# Power_Regulation.net
KiCad netlist of a schematic drawn in Altium Designer
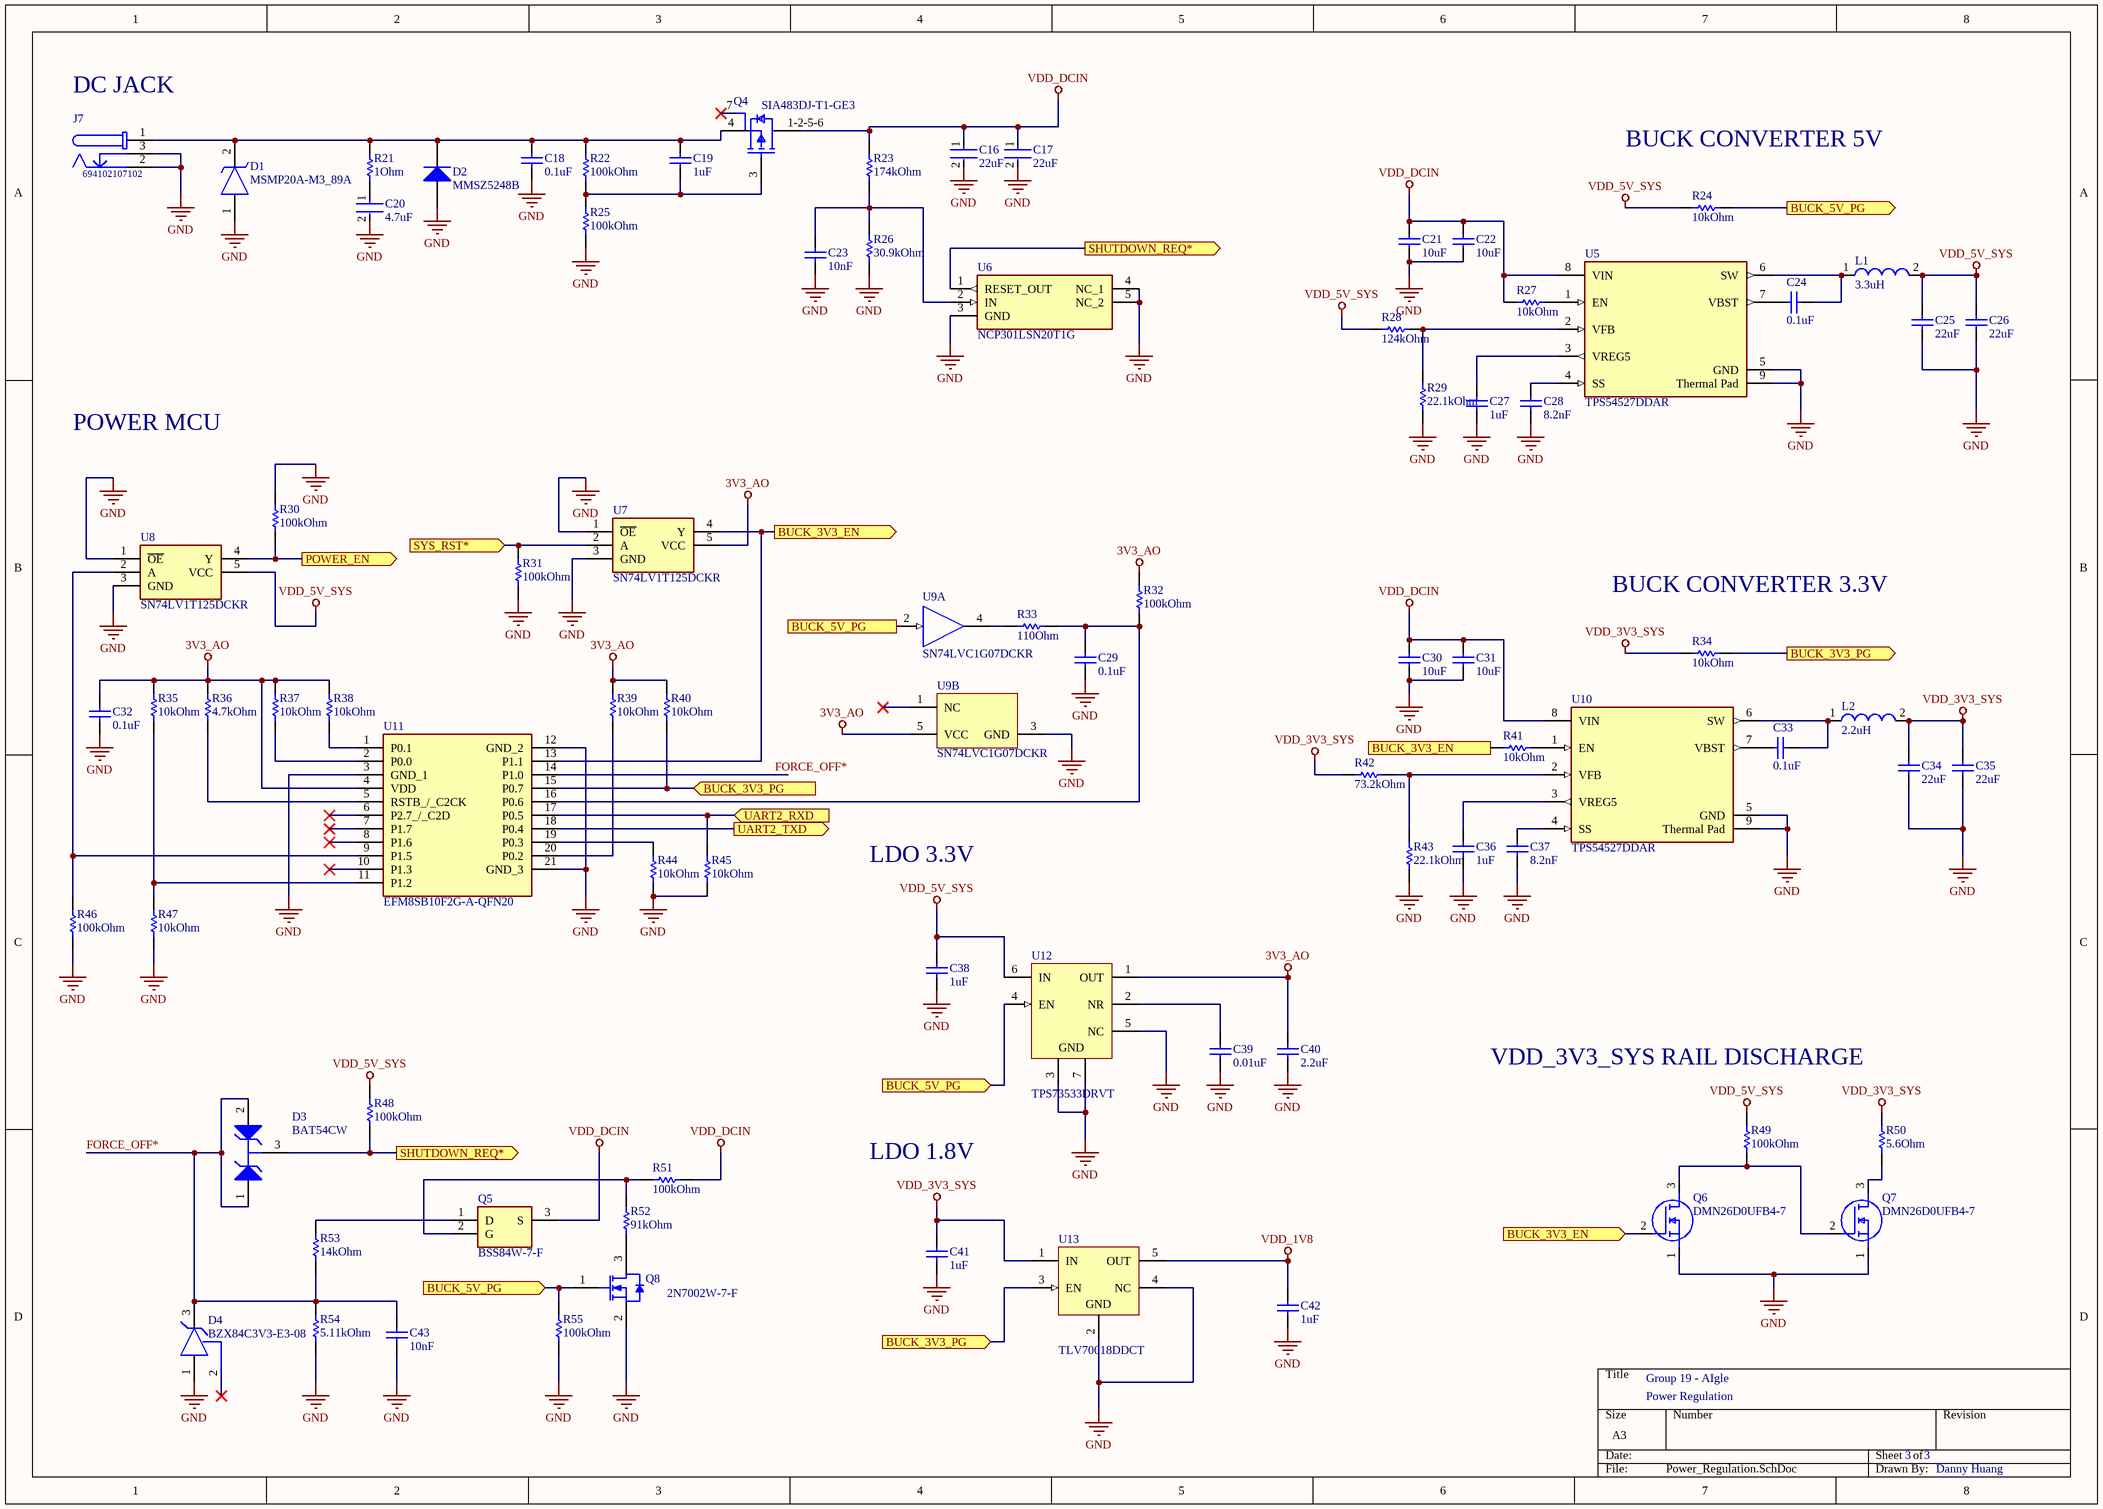
[diagram p0: Power_Regulation.SchDoc]

(export (version "E")
  (design (tool "Eeschema 10.0.6"))
  (components
    (comp (ref "C16")
      (value "22uF")
      (footprint "FP-GRM21-0_2-MFG")
      (description "CAP CER 22UF 25V X5R 0805")
      (fields (field (name "TOLERANCE") "20%") (field (name "MANUFACTURER PART NUMBER") "GRM21BR61E226ME44L"))
      (libsource (lib "Altium Content Vault") (part "b4654b650e69147ec39a6b967a45e02"))
    )
    (comp (ref "C17")
      (value "22uF")
      (footprint "FP-GRM21-0_2-MFG")
      (description "CAP CER 22UF 25V X5R 0805")
      (fields (field (name "TOLERANCE") "20%") (field (name "MANUFACTURER PART NUMBER") "GRM21BR61E226ME44L"))
      (libsource (lib "Altium Content Vault") (part "b4654b650e69147ec39a6b967a45e02"))
    )
    (comp (ref "C18")
      (value "0.1uF")
      (footprint "CAPC1005X55X30NL05T10")
      (fields (field (name "MANUFACTURER") "Kemet") (field (name "PART NUMBER") "C0402C104K9RACTU"))
      (libsource (lib "Altium Content Vault") (part "CAP"))
    )
    (comp (ref "C19")
      (value "1uF")
      (footprint "CAPC1608X90X35LL10T15")
      (fields (field (name "MANUFACTURER") "Murata") (field (name "PART NUMBER") "GRM188R61E105KA12D"))
      (libsource (lib "Altium Content Vault") (part "CAP"))
    )
    (comp (ref "C20")
      (value "4.7uF")
      (footprint "FP-C0603-CG-MFG")
      (description "CAP CER 4.7UF 6.3V X5R 0603")
      (fields (field (name "TOLERANCE") "10%") (field (name "MANUFACTURER") "Kemet"))
      (libsource (lib "Altium Content Vault") (part "11868f565c42a9108669ba33697ecf6"))
    )
    (comp (ref "C21")
      (value "10uF")
      (footprint "CAPC1608X90X35NL10T15")
      (fields (field (name "PART NUMBER") "GRM188R60J106ME47D") (field (name "MANUFACTURER") "Murata"))
      (libsource (lib "Altium Content Vault") (part "CAP"))
    )
    (comp (ref "C22")
      (value "10uF")
      (footprint "CAPC1608X90X35NL10T15")
      (fields (field (name "PART NUMBER") "GRM188R60J106ME47D") (field (name "MANUFACTURER") "Murata"))
      (libsource (lib "Altium Content Vault") (part "CAP"))
    )
    (comp (ref "C23")
      (value "10nF")
      (footprint "CAPC1005X55X30NL05T10")
      (fields (field (name "MANUFACTURER") "Kemet") (field (name "PART NUMBER") "C0402C103K4RACTU"))
      (libsource (lib "Altium Content Vault") (part "CAP"))
    )
    (comp (ref "C24")
      (value "0.1uF")
      (footprint "CAPC1005X55X30NL05T10")
      (fields (field (name "MANUFACTURER") "Kemet") (field (name "PART NUMBER") "C0402C104K9RACTU"))
      (libsource (lib "Altium Content Vault") (part "CAP"))
    )
    (comp (ref "C25")
      (value "22uF")
      (footprint "CAPC1608X100X20ML10")
      (description "Chip Capacitor, 22 uF, +/- 20%, 6.3 V, -55 to 85 degC, 1608 (0603 Metric), RoHS, Tape and Reel")
      (fields
        (field (name "TOLERANCE") "±20%")
        (field (name "PCN PART NUMBER") "MLCCPartNumberChange30/Nov/2012")
      )
      (libsource (lib "Altium Content Vault") (part "CAP-NP-2"))
    )
    (comp (ref "C26")
      (value "22uF")
      (footprint "CAPC1608X100X20ML10")
      (description "Chip Capacitor, 22 uF, +/- 20%, 6.3 V, -55 to 85 degC, 1608 (0603 Metric), RoHS, Tape and Reel")
      (fields
        (field (name "TOLERANCE") "±20%")
        (field (name "PCN PART NUMBER") "MLCCPartNumberChange30/Nov/2012")
      )
      (libsource (lib "Altium Content Vault") (part "CAP-NP-2"))
    )
    (comp (ref "C27")
      (value "1uF")
      (footprint "CAPC1005X60X30ML05T10")
      (fields (field (name "PART NUMBER") "C0402C105K9PAC7867") (field (name "MANUFACTURER") "Kemet"))
      (libsource (lib "Altium Content Vault") (part "CAP"))
    )
    (comp (ref "C28")
      (value "8.2nF")
      (footprint "CAPC1005X55X30ML05T10")
      (fields (field (name "PART NUMBER") "C0402C822K5RACTU") (field (name "MANUFACTURER") "Kemet"))
      (libsource (lib "Altium Content Vault") (part "CAP"))
    )
    (comp (ref "C29")
      (value "0.1uF")
      (footprint "CAPC1005X55X30NL05T10")
      (fields (field (name "MANUFACTURER") "Kemet") (field (name "PART NUMBER") "C0402C104K9RACTU"))
      (libsource (lib "Altium Content Vault") (part "CAP"))
    )
    (comp (ref "C30")
      (value "10uF")
      (footprint "CAPC1608X90X35NL10T15")
      (fields (field (name "PART NUMBER") "GRM188R60J106ME47D") (field (name "MANUFACTURER") "Murata"))
      (libsource (lib "Altium Content Vault") (part "CAP"))
    )
    (comp (ref "C31")
      (value "10uF")
      (footprint "CAPC1608X90X35NL10T15")
      (fields (field (name "PART NUMBER") "GRM188R60J106ME47D") (field (name "MANUFACTURER") "Murata"))
      (libsource (lib "Altium Content Vault") (part "CAP"))
    )
    (comp (ref "C32")
      (value "0.1uF")
      (footprint "CAPC1005X55X30NL05T10")
      (fields (field (name "MANUFACTURER") "Kemet") (field (name "PART NUMBER") "C0402C104K9RACTU"))
      (libsource (lib "Altium Content Vault") (part "CAP"))
    )
    (comp (ref "C33")
      (value "0.1uF")
      (footprint "CAPC1005X55X30NL05T10")
      (fields (field (name "MANUFACTURER") "Kemet") (field (name "PART NUMBER") "C0402C104K9RACTU"))
      (libsource (lib "Altium Content Vault") (part "CAP"))
    )
    (comp (ref "C34")
      (value "22uF")
      (footprint "CAPC1608X100X20ML10")
      (description "Chip Capacitor, 22 uF, +/- 20%, 6.3 V, -55 to 85 degC, 1608 (0603 Metric), RoHS, Tape and Reel")
      (fields
        (field (name "TOLERANCE") "±20%")
        (field (name "PCN PART NUMBER") "MLCCPartNumberChange30/Nov/2012")
      )
      (libsource (lib "Altium Content Vault") (part "CAP-NP-2"))
    )
    (comp (ref "C35")
      (value "22uF")
      (footprint "CAPC1608X100X20ML10")
      (description "Chip Capacitor, 22 uF, +/- 20%, 6.3 V, -55 to 85 degC, 1608 (0603 Metric), RoHS, Tape and Reel")
      (fields
        (field (name "TOLERANCE") "±20%")
        (field (name "PCN PART NUMBER") "MLCCPartNumberChange30/Nov/2012")
      )
      (libsource (lib "Altium Content Vault") (part "CAP-NP-2"))
    )
    (comp (ref "C36")
      (value "1uF")
      (footprint "CAPC1005X60X30ML05T10")
      (fields (field (name "PART NUMBER") "C0402C105K9PAC7867") (field (name "MANUFACTURER") "Kemet"))
      (libsource (lib "Altium Content Vault") (part "CAP"))
    )
    (comp (ref "C37")
      (value "8.2nF")
      (footprint "CAPC1005X55X30ML05T10")
      (fields (field (name "PART NUMBER") "C0402C822K5RACTU") (field (name "MANUFACTURER") "Kemet"))
      (libsource (lib "Altium Content Vault") (part "CAP"))
    )
    (comp (ref "C38")
      (value "1uF")
      (footprint "CAPC1005X60X30ML05T10")
      (fields (field (name "PART NUMBER") "C0402C105K9PAC7867") (field (name "MANUFACTURER") "Kemet"))
      (libsource (lib "Altium Content Vault") (part "CAP"))
    )
    (comp (ref "C39")
      (value "0.01uF")
      (footprint "CAPC1005X55X30LL05T10")
      (fields (field (name "MANUFACTURER") "Kemet") (field (name "PART NUMBER") "C0402C103K9RACTU"))
      (libsource (lib "Altium Content Vault") (part "CAP"))
    )
    (comp (ref "C40")
      (value "2.2uF")
      (footprint "CAPC1005X60X30NL05T10")
      (fields (field (name "PART NUMBER") "C0402C225K9PACTU") (field (name "MANUFACTURER") "Kemet"))
      (libsource (lib "Altium Content Vault") (part "CAP"))
    )
    (comp (ref "C41")
      (value "1uF")
      (footprint "CAPC1005X60X30ML05T10")
      (fields (field (name "PART NUMBER") "C0402C105K9PAC7867") (field (name "MANUFACTURER") "Kemet"))
      (libsource (lib "Altium Content Vault") (part "CAP"))
    )
    (comp (ref "C42")
      (value "1uF")
      (footprint "CAPC1005X60X30ML05T10")
      (fields (field (name "PART NUMBER") "C0402C105K9PAC7867") (field (name "MANUFACTURER") "Kemet"))
      (libsource (lib "Altium Content Vault") (part "CAP"))
    )
    (comp (ref "C43")
      (value "10nF")
      (footprint "CAPC1005X55X30NL05T10")
      (fields (field (name "MANUFACTURER") "Kemet") (field (name "PART NUMBER") "C0402C103K4RACTU"))
      (libsource (lib "Altium Content Vault") (part "CAP"))
    )
    (comp (ref "D1")
      (value "MSMP20A-M3_89A")
      (footprint "SamacSys:MICROSMP(ESMP)")
      (description "TVS Diode (Uni-directional)")
      (fields
        (field (name "MANUFACTURER_PART_NUMBER") "MSMP20A-M3/89A")
        (field (name "MOUSER PART NUMBER") "78-MSMP20A-M389A")
      )
      (libsource (lib "*") (part "MSMP20A-M3_89A"))
    )
    (comp (ref "D2")
      (value "MMSZ5248B")
      (footprint "FAIR-SOD-123-2_V")
      (description "Zener Diode, 18 V, -55 to 150 degC, 2-Pin SOD-123, RoHS, Tape and Reel")
      (fields (field (name "MANUFACTURER") "FairchildSemiconductor"))
      (libsource (lib "Altium Content Vault") (part "D-AK-2"))
    )
    (comp (ref "D3")
      (value "BAT54CW")
      (footprint "NXP-SOT323-3_L")
      (description "SOT-323 Plastic-Encapsulated Diode")
      (fields (field (name "MANUFACTURER") "NXP Semiconductors"))
      (libsource (lib "Altium Content Vault") (part "NXP-DSKY-A1K3-3"))
    )
    (comp (ref "D4")
      (value "BZX84C3V3-E3-08")
      (footprint "FP-6_541-5014_01-4-MFG")
      (description "DIODE ZENER 3.3V 300MW SOT23")
      (fields
        (field (name "MANUFACTURER") "Vishay")
        (field (name "OCTOPART") "https://octopart.com/bzx84c3v3-e3-08-vishay-30324846")
      )
      (libsource (lib "Altium Content Vault") (part "926c53f45a061d244664d41e4b83f83"))
    )
    (comp (ref "J7")
      (value "694102107102")
      (footprint "694102107102")
      (fields (field (name "MANUFACTURER") "Wurth Elektronik") (field (name "PUBLISHER") "WurthElektronik"))
      (libsource (lib "Altium Content Vault") (part "WE-JACK-2CD3-RN"))
    )
    (comp (ref "L1")
      (value "3.3uH")
      (footprint "SMD 0806")
      (description "Power Multilayer Inductor WE-PMI, L=3.30 µH")
      (fields (field (name "PARTNUMBER") "74479776233") (field (name "MANUFACTURER") "Wuerth Elektronik"))
      (libsource (lib "Altium Content Vault") (part "PAS-IND-INDUCTOR-2"))
    )
    (comp (ref "L2")
      (value "2.2uH")
      (footprint "SMD 0805-Low profile")
      (description "Power Multilayer Inductor WE-PMI, L=2.20 µH")
      (fields (field (name "MANUFACTURER") "Wuerth Elektronik") (field (name "PARTNUMBER") "74479774222"))
      (libsource (lib "Altium Content Vault") (part "PAS-IND-INDUCTOR-2"))
    )
    (comp (ref "Q4")
      (value "SIA483DJ-T1-GE3")
      (footprint "FP-C-07431-MFG")
      (description "MOSFET P-CH 30V 12A SC70-6")
      (fields
        (field (name "OCTOPART") "https://octopart.com/sia483dj-t1-ge3-vishay-45727624")
        (field (name "MANUFACTURER") "Vishay")
      )
      (libsource (lib "Altium Content Vault") (part "150fc967241ccd8041086e7d050c159"))
    )
    (comp (ref "Q5")
      (value "BSS84W-7-F")
      (footprint "SamacSys:SOT65P210X110-3N")
      (description "Undefined or Miscellaneous")
      (fields (field (name "MOUSER PART NUMBER") "621-BSS84W-F"))
      (libsource (lib "*") (part "BSS84W-7-F"))
    )
    (comp (ref "Q6")
      (value "DMN26D0UFB4-7")
      (footprint "SamacSys:DMN26D0UFB47")
      (description "MOSFET (N-Channel)")
      (fields (field (name "MOUSER PART NUMBER") "621-DMN26D0UFB4-7"))
      (libsource (lib "*") (part "DMN26D0UFB4-7"))
    )
    (comp (ref "Q7")
      (value "DMN26D0UFB4-7")
      (footprint "SamacSys:DMN26D0UFB47")
      (description "MOSFET (N-Channel)")
      (fields (field (name "MOUSER PART NUMBER") "621-DMN26D0UFB4-7"))
      (libsource (lib "*") (part "DMN26D0UFB4-7"))
    )
    (comp (ref "Q8")
      (value "2N7002W-7-F")
      (footprint "DIOD-SOT323-3_V")
      (fields (field (name "MANUFACTURER") "DiodesIncorporated"))
      (libsource (lib "Altium Content Vault") (part "NEMOS-GSD-3"))
    )
    (comp (ref "R21")
      (value "1Ohm")
      (footprint "RESC1005X40X25ML05T05")
      (fields (field (name "PART NUMBER") "CRCW04021R00FKED") (field (name "MANUFACTURER") "Vishay Dale"))
      (libsource (lib "Altium Content Vault") (part "RES"))
    )
    (comp (ref "R22")
      (value "100kOhm")
      (footprint "RESC1005X40X25ML05T05")
      (description "Chip Resistor, 100 KOhm, +/- 1%, 0.63 W, -55 to 155 degC, 0402 (1005 Metric), RoHS, Tape and Reel")
      (fields (field (name "TOLERANCE") "1%"))
      (libsource (lib "Altium Content Vault") (part "RES-2"))
    )
    (comp (ref "R23")
      (value "174kOhm")
      (footprint "RESC1005X40X25LL05T05")
      (fields (field (name "MANUFACTURER") "Vishay Dale") (field (name "PART NUMBER") "CRCW0402174KFKED"))
      (libsource (lib "Altium Content Vault") (part "RES"))
    )
    (comp (ref "R24")
      (value "10kOhm")
      (footprint "RESC1005X40X25NL05T05")
      (fields (field (name "MANUFACTURER") "Vishay Dale") (field (name "PART NUMBER") "CRCW040210K0JNED"))
      (libsource (lib "Altium Content Vault") (part "RES"))
    )
    (comp (ref "R25")
      (value "100kOhm")
      (footprint "RESC1005X40X25ML05T05")
      (description "Chip Resistor, 100 KOhm, +/- 1%, 0.63 W, -55 to 155 degC, 0402 (1005 Metric), RoHS, Tape and Reel")
      (fields (field (name "TOLERANCE") "1%"))
      (libsource (lib "Altium Content Vault") (part "RES-2"))
    )
    (comp (ref "R26")
      (value "30.9kOhm")
      (footprint "RESC1005X40X25LL05T05")
      (fields (field (name "PART NUMBER") "CRCW040230K9FKED") (field (name "MANUFACTURER") "Vishay Dale"))
      (libsource (lib "Altium Content Vault") (part "RES"))
    )
    (comp (ref "R27")
      (value "10kOhm")
      (footprint "RESC1005X40X25NL05T05")
      (fields (field (name "MANUFACTURER") "Vishay Dale") (field (name "PART NUMBER") "CRCW040210K0JNED"))
      (libsource (lib "Altium Content Vault") (part "RES"))
    )
    (comp (ref "R28")
      (value "124kOhm")
      (footprint "RESC1005X40X25ML05T05")
      (fields (field (name "MANUFACTURER") "Vishay Dale") (field (name "PART NUMBER") "CRCW0402124KFKED"))
      (libsource (lib "Altium Content Vault") (part "RES"))
    )
    (comp (ref "R29")
      (value "22.1kOhm")
      (footprint "RESC1005X40X25ML05T05")
      (fields (field (name "MANUFACTURER") "Vishay Dale") (field (name "PART NUMBER") "CRCW040222K1FKED"))
      (libsource (lib "Altium Content Vault") (part "RES"))
    )
    (comp (ref "R30")
      (value "100kOhm")
      (footprint "RESC1005X40X25ML05T05")
      (description "Chip Resistor, 100 KOhm, +/- 1%, 0.63 W, -55 to 155 degC, 0402 (1005 Metric), RoHS, Tape and Reel")
      (fields (field (name "TOLERANCE") "1%"))
      (libsource (lib "Altium Content Vault") (part "RES-2"))
    )
    (comp (ref "R31")
      (value "100kOhm")
      (footprint "RESC1005X40X25ML05T05")
      (description "Chip Resistor, 100 KOhm, +/- 1%, 0.63 W, -55 to 155 degC, 0402 (1005 Metric), RoHS, Tape and Reel")
      (fields (field (name "TOLERANCE") "1%"))
      (libsource (lib "Altium Content Vault") (part "RES-2"))
    )
    (comp (ref "R32")
      (value "100kOhm")
      (footprint "RESC1005X40X25ML05T05")
      (description "Chip Resistor, 100 KOhm, +/- 1%, 0.63 W, -55 to 155 degC, 0402 (1005 Metric), RoHS, Tape and Reel")
      (fields (field (name "TOLERANCE") "1%"))
      (libsource (lib "Altium Content Vault") (part "RES-2"))
    )
    (comp (ref "R33")
      (value "110Ohm")
      (footprint "RESC1005X40X25LL05T05")
      (fields (field (name "PART NUMBER") "CRCW0402110RJNED") (field (name "MANUFACTURER") "Vishay Dale"))
      (libsource (lib "Altium Content Vault") (part "RES"))
    )
    (comp (ref "R34")
      (value "10kOhm")
      (footprint "RESC1005X40X25NL05T05")
      (fields (field (name "MANUFACTURER") "Vishay Dale") (field (name "PART NUMBER") "CRCW040210K0JNED"))
      (libsource (lib "Altium Content Vault") (part "RES"))
    )
    (comp (ref "R35")
      (value "10kOhm")
      (footprint "RESC1005X40X25NL05T05")
      (fields (field (name "MANUFACTURER") "Vishay Dale") (field (name "PART NUMBER") "CRCW040210K0FKED"))
      (libsource (lib "Altium Content Vault") (part "RES"))
    )
    (comp (ref "R36")
      (value "4.7kOhm")
      (footprint "RESC1005X40X25ML05T05")
      (fields
        (field (name "PART NUMBER") "CRCW04024K70JNED")
        (field (name "MANUFACTURER") "Vishay BCcomponents")
      )
      (libsource (lib "Altium Content Vault") (part "RES"))
    )
    (comp (ref "R37")
      (value "10kOhm")
      (footprint "RESC1005X40X25NL05T05")
      (fields (field (name "MANUFACTURER") "Vishay Dale") (field (name "PART NUMBER") "CRCW040210K0FKED"))
      (libsource (lib "Altium Content Vault") (part "RES"))
    )
    (comp (ref "R38")
      (value "10kOhm")
      (footprint "RESC1005X40X25NL05T05")
      (fields (field (name "MANUFACTURER") "Vishay Dale") (field (name "PART NUMBER") "CRCW040210K0FKED"))
      (libsource (lib "Altium Content Vault") (part "RES"))
    )
    (comp (ref "R39")
      (value "10kOhm")
      (footprint "RESC1005X40X25NL05T05")
      (fields (field (name "MANUFACTURER") "Vishay Dale") (field (name "PART NUMBER") "CRCW040210K0FKED"))
      (libsource (lib "Altium Content Vault") (part "RES"))
    )
    (comp (ref "R40")
      (value "10kOhm")
      (footprint "RESC1005X40X25NL05T05")
      (fields (field (name "MANUFACTURER") "Vishay Dale") (field (name "PART NUMBER") "CRCW040210K0FKED"))
      (libsource (lib "Altium Content Vault") (part "RES"))
    )
    (comp (ref "R41")
      (value "10kOhm")
      (footprint "RESC1005X40X25NL05T05")
      (fields (field (name "MANUFACTURER") "Vishay Dale") (field (name "PART NUMBER") "CRCW040210K0JNED"))
      (libsource (lib "Altium Content Vault") (part "RES"))
    )
    (comp (ref "R42")
      (value "73.2kOhm")
      (footprint "RESC1005X40X25ML05T05")
      (fields (field (name "PART NUMBER") "CRCW040273K2FKED") (field (name "MANUFACTURER") "Vishay Dale"))
      (libsource (lib "Altium Content Vault") (part "RES"))
    )
    (comp (ref "R43")
      (value "22.1kOhm")
      (footprint "RESC1005X40X25ML05T05")
      (fields (field (name "MANUFACTURER") "Vishay Dale") (field (name "PART NUMBER") "CRCW040222K1FKED"))
      (libsource (lib "Altium Content Vault") (part "RES"))
    )
    (comp (ref "R44")
      (value "10kOhm")
      (footprint "RESC1005X40X25NL05T05")
      (fields (field (name "MANUFACTURER") "Vishay Dale") (field (name "PART NUMBER") "CRCW040210K0FKED"))
      (libsource (lib "Altium Content Vault") (part "RES"))
    )
    (comp (ref "R45")
      (value "10kOhm")
      (footprint "RESC1005X40X25NL05T05")
      (fields (field (name "MANUFACTURER") "Vishay Dale") (field (name "PART NUMBER") "CRCW040210K0FKED"))
      (libsource (lib "Altium Content Vault") (part "RES"))
    )
    (comp (ref "R46")
      (value "100kOhm")
      (footprint "RESC1005X40X25ML05T05")
      (description "Chip Resistor, 100 KOhm, +/- 1%, 0.63 W, -55 to 155 degC, 0402 (1005 Metric), RoHS, Tape and Reel")
      (fields (field (name "TOLERANCE") "1%"))
      (libsource (lib "Altium Content Vault") (part "RES-2"))
    )
    (comp (ref "R47")
      (value "10kOhm")
      (footprint "RESC1005X40X25NL05T05")
      (fields (field (name "MANUFACTURER") "Vishay Dale") (field (name "PART NUMBER") "CRCW040210K0FKED"))
      (libsource (lib "Altium Content Vault") (part "RES"))
    )
    (comp (ref "R48")
      (value "100kOhm")
      (footprint "RESC1005X40X25ML05T05")
      (description "Chip Resistor, 100 KOhm, +/- 1%, 0.63 W, -55 to 155 degC, 0402 (1005 Metric), RoHS, Tape and Reel")
      (fields (field (name "TOLERANCE") "1%"))
      (libsource (lib "Altium Content Vault") (part "RES-2"))
    )
    (comp (ref "R49")
      (value "100kOhm")
      (footprint "RESC1005X40X25ML05T05")
      (description "Chip Resistor, 100 KOhm, +/- 1%, 0.63 W, -55 to 155 degC, 0402 (1005 Metric), RoHS, Tape and Reel")
      (fields (field (name "TOLERANCE") "1%"))
      (libsource (lib "Altium Content Vault") (part "RES-2"))
    )
    (comp (ref "R50")
      (value "5.6Ohm")
      (footprint "RESC1005X40X25ML05T05")
      (fields (field (name "PART NUMBER") "ERJ-2GEJ5R6X") (field (name "MANUFACTURER") "Panasonic"))
      (libsource (lib "Altium Content Vault") (part "RES"))
    )
    (comp (ref "R51")
      (value "100kOhm")
      (footprint "RESC1005X40X25ML05T05")
      (description "Chip Resistor, 100 KOhm, +/- 1%, 0.63 W, -55 to 155 degC, 0402 (1005 Metric), RoHS, Tape and Reel")
      (fields (field (name "TOLERANCE") "1%"))
      (libsource (lib "Altium Content Vault") (part "RES-2"))
    )
    (comp (ref "R52")
      (value "91kOhm")
      (footprint "RESC1005X40X25ML05T05")
      (fields (field (name "MANUFACTURER") "Vishay Dale") (field (name "PART NUMBER") "CRCW040291K0JNED"))
      (libsource (lib "Altium Content Vault") (part "RES"))
    )
    (comp (ref "R53")
      (value "14kOhm")
      (footprint "RESC1005X40X25LL05T05")
      (fields (field (name "MANUFACTURER") "Vishay Dale") (field (name "PART NUMBER") "CRCW040214K0FKED"))
      (libsource (lib "Altium Content Vault") (part "RES"))
    )
    (comp (ref "R54")
      (value "5.11kOhm")
      (footprint "RESC1005X40X25LL05T05")
      (fields (field (name "MANUFACTURER") "Vishay Dale") (field (name "PART NUMBER") "CRCW04025K11FKED"))
      (libsource (lib "Altium Content Vault") (part "RES"))
    )
    (comp (ref "R55")
      (value "100kOhm")
      (footprint "RESC1005X40X25ML05T05")
      (description "Chip Resistor, 100 KOhm, +/- 1%, 0.63 W, -55 to 155 degC, 0402 (1005 Metric), RoHS, Tape and Reel")
      (fields (field (name "TOLERANCE") "1%"))
      (libsource (lib "Altium Content Vault") (part "RES-2"))
    )
    (comp (ref "U5")
      (value "TPS54527DDAR")
      (footprint "FP-DDA0008E-MFG")
      (description "IC REG BUCK ADJUSTABLE 5A 8SOPWR")
      (fields
        (field (name "OCTOPART") "https://octopart.com/tps54527ddar-texas+instruments-20362751")
        (field (name "MANUFACTURER") "Texas Instruments")
      )
      (libsource (lib "Altium Content Vault") (part "5ee31ad572399e68e8e3131d2eca248"))
    )
    (comp (ref "U6")
      (value "NCP301LSN20T1G")
      (footprint "SamacSys:SOT95P275X110-5N")
      (description "Integrated Circuit")
      (fields (field (name "MOUSER PART NUMBER") "863-NCP301LSN20T1G"))
      (libsource (lib "*") (part "NCP301LSN20T1G"))
    )
    (comp (ref "U7")
      (value "SN74LV1T125DCKR")
      (footprint "SamacSys:SOT65P210X110-5N")
      (description "Integrated Circuit")
      (fields (field (name "MOUSER PART NUMBER") "595-SN74LV1T125DCKR"))
      (libsource (lib "*") (part "SN74LV1T125DCKR"))
    )
    (comp (ref "U8")
      (value "SN74LV1T125DCKR")
      (footprint "SamacSys:SOT65P210X110-5N")
      (description "Integrated Circuit")
      (fields (field (name "MOUSER PART NUMBER") "595-SN74LV1T125DCKR"))
      (libsource (lib "*") (part "SN74LV1T125DCKR"))
    )
    (comp (ref "U9")
      (value "SN74LVC1G07DCKR")
      (footprint "DCK0005A_M")
      (description "Single Buffer/Driver With Open-Drain Output, DCK0005A, LARGE T&R")
      (fields
        (field (name "GENERIC PART NUMBER") "SN74LVC1G07")
        (field (name "MANUFACTURER") "Texas Instruments")
      )
      (libsource (lib "Altium Content Vault") (part "TI-SN74XXX1G07-5"))
    )
    (comp (ref "U10")
      (value "TPS54527DDAR")
      (footprint "FP-DDA0008E-MFG")
      (description "IC REG BUCK ADJUSTABLE 5A 8SOPWR")
      (fields
        (field (name "OCTOPART") "https://octopart.com/tps54527ddar-texas+instruments-20362751")
        (field (name "MANUFACTURER") "Texas Instruments")
      )
      (libsource (lib "Altium Content Vault") (part "5ee31ad572399e68e8e3131d2eca248"))
    )
    (comp (ref "U11")
      (value "EFM8SB10F2G-A-QFN20")
      (footprint "SamacSys:EFM8SB10F8GAQFN20R")
      (description "Integrated Circuit")
      (fields (field (name "MOUSER PART NUMBER") "634-8SB10F2GAQF20"))
      (libsource (lib "*") (part "EFM8SB10F2G-A-QFN20"))
    )
    (comp (ref "U12")
      (value "TPS73533DRVT")
      (footprint "DRV0006A_V")
      (fields (field (name "MANUFACTURER") "Texas Instruments"))
      (libsource (lib "Altium Content Vault") (part "TI-TPS7XXXXX-DRV6-1600X1000TP"))
    )
    (comp (ref "U13")
      (value "TLV70018DDCT")
      (footprint "DDC0005A_L")
      (fields (field (name "MANUFACTURER") "Texas Instruments"))
      (libsource (lib "Altium Content Vault") (part "TI-TXX7XXXX-5"))
    )
  )
  (nets
    (net (code "1") (name "/BUCK_3V3_EN") (class "Default")
      (node (ref "Q6") (pin "2") (pinfunction "G_2") (pintype "passive"))
      (node (ref "R41") (pin "2") (pinfunction "2_2") (pintype "passive"))
      (node (ref "U11") (pin "13") (pinfunction "P1.1_13") (pintype "passive"))
      (node (ref "U7") (pin "4") (pinfunction "Y_4") (pintype "passive"))
    )
    (net (code "2") (name "/BUCK_3V3_PG") (class "Default")
      (node (ref "R34") (pin "1") (pinfunction "1_1") (pintype "passive"))
      (node (ref "R40") (pin "1") (pinfunction "1_1") (pintype "passive"))
      (node (ref "U11") (pin "15") (pinfunction "P0.7_15") (pintype "passive"))
      (node (ref "U13") (pin "3") (pinfunction "EN_3") (pintype "input"))
    )
    (net (code "3") (name "/BUCK_5V_PG") (class "Default")
      (node (ref "Q8") (pin "1") (pinfunction "G_1") (pintype "passive"))
      (node (ref "R24") (pin "1") (pinfunction "1_1") (pintype "passive"))
      (node (ref "R55") (pin "2") (pinfunction "2_2") (pintype "passive"))
      (node (ref "U12") (pin "4") (pinfunction "EN_4") (pintype "input"))
      (node (ref "U9") (pin "2") (pinfunction "A_2") (pintype "input"))
    )
    (net (code "4") (name "/FORCE_OFF*") (class "Default")
      (node (ref "C43") (pin "2") (pinfunction "2_2") (pintype "passive"))
      (node (ref "D3") (pin "1") (pinfunction "A1_1") (pintype "passive"))
      (node (ref "D3") (pin "2") (pinfunction "A2_2") (pintype "passive"))
      (node (ref "D4") (pin "3") (pinfunction "C_3") (pintype "passive"))
      (node (ref "R53") (pin "1") (pinfunction "1_1") (pintype "passive"))
      (node (ref "R54") (pin "2") (pinfunction "2_2") (pintype "passive"))
      (node (ref "U11") (pin "14") (pinfunction "P1.0_14") (pintype "passive"))
    )
    (net (code "5") (name "/POWER_EN") (class "Default")
      (node (ref "R30") (pin "1") (pinfunction "1_1") (pintype "passive"))
      (node (ref "U8") (pin "4") (pinfunction "Y_4") (pintype "passive"))
    )
    (net (code "6") (name "/SHUTDOWN_REQ*") (class "Default")
      (node (ref "D3") (pin "3") (pinfunction "K_3") (pintype "passive"))
      (node (ref "R48") (pin "1") (pinfunction "1_1") (pintype "passive"))
      (node (ref "U6") (pin "1") (pinfunction "RESET_OUT_1") (pintype "output"))
    )
    (net (code "7") (name "/SYS_RST*") (class "Default")
      (node (ref "R31") (pin "2") (pinfunction "2_2") (pintype "passive"))
      (node (ref "U7") (pin "2") (pinfunction "A_2") (pintype "passive"))
    )
    (net (code "8") (name "/UART2_RXD") (class "Default")
      (node (ref "R45") (pin "2") (pinfunction "2_2") (pintype "passive"))
      (node (ref "U11") (pin "17") (pinfunction "P0.5_17") (pintype "passive"))
    )
    (net (code "9") (name "/UART2_TXD") (class "Default")
      (node (ref "U11") (pin "18") (pinfunction "P0.4_18") (pintype "passive"))
    )
    (net (code "10") (name "3V3_AO") (class "Default")
      (node (ref "C32") (pin "1") (pinfunction "1_1") (pintype "passive"))
      (node (ref "C40") (pin "2") (pinfunction "2_2") (pintype "passive"))
      (node (ref "R32") (pin "2") (pinfunction "2_2") (pintype "passive"))
      (node (ref "R35") (pin "2") (pinfunction "2_2") (pintype "passive"))
      (node (ref "R36") (pin "2") (pinfunction "2_2") (pintype "passive"))
      (node (ref "R37") (pin "2") (pinfunction "2_2") (pintype "passive"))
      (node (ref "R38") (pin "2") (pinfunction "2_2") (pintype "passive"))
      (node (ref "R39") (pin "2") (pinfunction "2_2") (pintype "passive"))
      (node (ref "R40") (pin "2") (pinfunction "2_2") (pintype "passive"))
      (node (ref "U11") (pin "4") (pinfunction "VDD_4") (pintype "passive"))
      (node (ref "U12") (pin "1") (pinfunction "OUT_1") (pintype "power_in"))
      (node (ref "U7") (pin "5") (pinfunction "VCC_5") (pintype "passive"))
      (node (ref "U9") (pin "5") (pinfunction "VCC_5") (pintype "power_in"))
    )
    (net (code "11") (name "GND") (class "Default")
      (node (ref "C16") (pin "2") (pinfunction "2_2") (pintype "passive"))
      (node (ref "C17") (pin "2") (pinfunction "2_2") (pintype "passive"))
      (node (ref "C18") (pin "2") (pinfunction "2_2") (pintype "passive"))
      (node (ref "C20") (pin "2") (pinfunction "2_2") (pintype "passive"))
      (node (ref "C21") (pin "1") (pinfunction "1_1") (pintype "passive"))
      (node (ref "C22") (pin "1") (pinfunction "1_1") (pintype "passive"))
      (node (ref "C23") (pin "1") (pinfunction "1_1") (pintype "passive"))
      (node (ref "C25") (pin "1") (pinfunction "1_1") (pintype "passive"))
      (node (ref "C26") (pin "1") (pinfunction "1_1") (pintype "passive"))
      (node (ref "C27") (pin "1") (pinfunction "1_1") (pintype "passive"))
      (node (ref "C28") (pin "1") (pinfunction "1_1") (pintype "passive"))
      (node (ref "C29") (pin "2") (pinfunction "2_2") (pintype "passive"))
      (node (ref "C30") (pin "1") (pinfunction "1_1") (pintype "passive"))
      (node (ref "C31") (pin "1") (pinfunction "1_1") (pintype "passive"))
      (node (ref "C32") (pin "2") (pinfunction "2_2") (pintype "passive"))
      (node (ref "C34") (pin "1") (pinfunction "1_1") (pintype "passive"))
      (node (ref "C35") (pin "1") (pinfunction "1_1") (pintype "passive"))
      (node (ref "C36") (pin "1") (pinfunction "1_1") (pintype "passive"))
      (node (ref "C37") (pin "1") (pinfunction "1_1") (pintype "passive"))
      (node (ref "C38") (pin "1") (pinfunction "1_1") (pintype "passive"))
      (node (ref "C39") (pin "1") (pinfunction "1_1") (pintype "passive"))
      (node (ref "C40") (pin "1") (pinfunction "1_1") (pintype "passive"))
      (node (ref "C41") (pin "1") (pinfunction "1_1") (pintype "passive"))
      (node (ref "C42") (pin "1") (pinfunction "1_1") (pintype "passive"))
      (node (ref "C43") (pin "1") (pinfunction "1_1") (pintype "passive"))
      (node (ref "D1") (pin "1") (pinfunction "A_1") (pintype "passive"))
      (node (ref "D2") (pin "1") (pinfunction "A_1") (pintype "passive"))
      (node (ref "D4") (pin "1") (pinfunction "A_1") (pintype "passive"))
      (node (ref "J7") (pin "2") (pinfunction "2_2") (pintype "passive"))
      (node (ref "J7") (pin "3") (pinfunction "3_3") (pintype "passive"))
      (node (ref "Q6") (pin "1") (pinfunction "S_1") (pintype "passive"))
      (node (ref "Q7") (pin "1") (pinfunction "S_1") (pintype "passive"))
      (node (ref "Q8") (pin "2") (pinfunction "S_2") (pintype "passive"))
      (node (ref "R25") (pin "2") (pinfunction "2_2") (pintype "passive"))
      (node (ref "R26") (pin "1") (pinfunction "1_1") (pintype "passive"))
      (node (ref "R29") (pin "1") (pinfunction "1_1") (pintype "passive"))
      (node (ref "R30") (pin "2") (pinfunction "2_2") (pintype "passive"))
      (node (ref "R31") (pin "1") (pinfunction "1_1") (pintype "passive"))
      (node (ref "R43") (pin "1") (pinfunction "1_1") (pintype "passive"))
      (node (ref "R44") (pin "1") (pinfunction "1_1") (pintype "passive"))
      (node (ref "R45") (pin "1") (pinfunction "1_1") (pintype "passive"))
      (node (ref "R46") (pin "1") (pinfunction "1_1") (pintype "passive"))
      (node (ref "R47") (pin "1") (pinfunction "1_1") (pintype "passive"))
      (node (ref "R54") (pin "1") (pinfunction "1_1") (pintype "passive"))
      (node (ref "R55") (pin "1") (pinfunction "1_1") (pintype "passive"))
      (node (ref "U10") (pin "5") (pinfunction "GND_5") (pintype "power_in"))
      (node (ref "U10") (pin "9") (pinfunction "Thermal_Pad_9") (pintype "power_in"))
      (node (ref "U11") (pin "12") (pinfunction "GND_2_12") (pintype "passive"))
      (node (ref "U11") (pin "21") (pinfunction "GND_3_21") (pintype "passive"))
      (node (ref "U11") (pin "3") (pinfunction "GND_1_3") (pintype "passive"))
      (node (ref "U12") (pin "3") (pinfunction "GND_3") (pintype "power_in"))
      (node (ref "U12") (pin "5") (pinfunction "NC_5") (pintype "passive"))
      (node (ref "U12") (pin "7") (pinfunction "GND_7") (pintype "power_in"))
      (node (ref "U13") (pin "2") (pinfunction "GND_2") (pintype "power_in"))
      (node (ref "U13") (pin "4") (pinfunction "NC_4") (pintype "passive"))
      (node (ref "U5") (pin "5") (pinfunction "GND_5") (pintype "power_in"))
      (node (ref "U5") (pin "9") (pinfunction "Thermal_Pad_9") (pintype "power_in"))
      (node (ref "U6") (pin "3") (pinfunction "GND_3") (pintype "power_in"))
      (node (ref "U6") (pin "4") (pinfunction "NC_1_4") (pintype "passive"))
      (node (ref "U6") (pin "5") (pinfunction "NC_2_5") (pintype "passive"))
      (node (ref "U7") (pin "1") (pinfunction "~{OE}_1") (pintype "passive"))
      (node (ref "U7") (pin "3") (pinfunction "GND_3") (pintype "passive"))
      (node (ref "U8") (pin "1") (pinfunction "~{OE}_1") (pintype "passive"))
      (node (ref "U8") (pin "3") (pinfunction "GND_3") (pintype "passive"))
      (node (ref "U9") (pin "3") (pinfunction "GND_3") (pintype "power_in"))
    )
    (net (code "12") (name "Net-(C20-Pad1)") (class "Default")
      (node (ref "C20") (pin "1") (pinfunction "1_1") (pintype "passive"))
      (node (ref "R21") (pin "1") (pinfunction "1_1") (pintype "passive"))
    )
    (net (code "13") (name "Net-(D1-K)") (class "Default")
      (node (ref "C18") (pin "1") (pinfunction "1_1") (pintype "passive"))
      (node (ref "C19") (pin "2") (pinfunction "2_2") (pintype "passive"))
      (node (ref "D1") (pin "2") (pinfunction "K_2") (pintype "passive"))
      (node (ref "D2") (pin "2") (pinfunction "K_2") (pintype "passive"))
      (node (ref "J7") (pin "1") (pinfunction "1_1") (pintype "passive"))
      (node (ref "Q4") (pin "4") (pinfunction "S_4") (pintype "passive"))
      (node (ref "R21") (pin "2") (pinfunction "2_2") (pintype "passive"))
      (node (ref "R22") (pin "1") (pinfunction "1_1") (pintype "passive"))
    )
    (net (code "14") (name "Net-(Q4-G)") (class "Default")
      (node (ref "C19") (pin "1") (pinfunction "1_1") (pintype "passive"))
      (node (ref "Q4") (pin "3") (pinfunction "G_3") (pintype "passive"))
      (node (ref "R22") (pin "2") (pinfunction "2_2") (pintype "passive"))
      (node (ref "R25") (pin "1") (pinfunction "1_1") (pintype "passive"))
    )
    (net (code "15") (name "Net-(Q5-D)") (class "Default")
      (node (ref "Q5") (pin "1") (pinfunction "D_1") (pintype "passive"))
      (node (ref "R53") (pin "2") (pinfunction "2_2") (pintype "passive"))
    )
    (net (code "16") (name "Net-(Q5-G)") (class "Default")
      (node (ref "Q5") (pin "2") (pinfunction "G_2") (pintype "passive"))
      (node (ref "R51") (pin "2") (pinfunction "2_2") (pintype "passive"))
      (node (ref "R52") (pin "2") (pinfunction "2_2") (pintype "passive"))
    )
    (net (code "17") (name "Net-(Q6-D)") (class "Default")
      (node (ref "Q6") (pin "3") (pinfunction "D_3") (pintype "passive"))
      (node (ref "Q7") (pin "2") (pinfunction "G_2") (pintype "passive"))
      (node (ref "R49") (pin "1") (pinfunction "1_1") (pintype "passive"))
    )
    (net (code "18") (name "Net-(Q7-D)") (class "Default")
      (node (ref "Q7") (pin "3") (pinfunction "D_3") (pintype "passive"))
      (node (ref "R50") (pin "1") (pinfunction "1_1") (pintype "passive"))
    )
    (net (code "19") (name "Net-(Q8-D)") (class "Default")
      (node (ref "Q8") (pin "3") (pinfunction "D_3") (pintype "passive"))
      (node (ref "R52") (pin "1") (pinfunction "1_1") (pintype "passive"))
    )
    (net (code "20") (name "Net-(U5-EN)") (class "Default")
      (node (ref "R27") (pin "1") (pinfunction "1_1") (pintype "passive"))
      (node (ref "U5") (pin "1") (pinfunction "EN_1") (pintype "input"))
    )
    (net (code "21") (name "Net-(U5-SS)") (class "Default")
      (node (ref "C28") (pin "2") (pinfunction "2_2") (pintype "passive"))
      (node (ref "U5") (pin "4") (pinfunction "SS_4") (pintype "input"))
    )
    (net (code "22") (name "Net-(U5-SW)") (class "Default")
      (node (ref "C24") (pin "1") (pinfunction "1_1") (pintype "passive"))
      (node (ref "L1") (pin "1") (pinfunction "1_1") (pintype "passive"))
      (node (ref "U5") (pin "6") (pinfunction "SW_6") (pintype "output"))
    )
    (net (code "23") (name "Net-(U5-VBST)") (class "Default")
      (node (ref "C24") (pin "2") (pinfunction "2_2") (pintype "passive"))
      (node (ref "U5") (pin "7") (pinfunction "VBST_7") (pintype "output"))
    )
    (net (code "24") (name "Net-(U5-VFB)") (class "Default")
      (node (ref "R28") (pin "2") (pinfunction "2_2") (pintype "passive"))
      (node (ref "R29") (pin "2") (pinfunction "2_2") (pintype "passive"))
      (node (ref "U5") (pin "2") (pinfunction "VFB_2") (pintype "input"))
    )
    (net (code "25") (name "Net-(U5-VREG5)") (class "Default")
      (node (ref "C27") (pin "2") (pinfunction "2_2") (pintype "passive"))
      (node (ref "U5") (pin "3") (pinfunction "VREG5_3") (pintype "output"))
    )
    (net (code "26") (name "Net-(U6-IN)") (class "Default")
      (node (ref "C23") (pin "2") (pinfunction "2_2") (pintype "passive"))
      (node (ref "R23") (pin "1") (pinfunction "1_1") (pintype "passive"))
      (node (ref "R26") (pin "2") (pinfunction "2_2") (pintype "passive"))
      (node (ref "U6") (pin "2") (pinfunction "IN_2") (pintype "input"))
    )
    (net (code "27") (name "Net-(U9A-Y)") (class "Default")
      (node (ref "R33") (pin "1") (pinfunction "1_1") (pintype "passive"))
      (node (ref "U9") (pin "4") (pinfunction "Y_4") (pintype "open_collector"))
    )
    (net (code "28") (name "Net-(U10-EN)") (class "Default")
      (node (ref "R41") (pin "1") (pinfunction "1_1") (pintype "passive"))
      (node (ref "U10") (pin "1") (pinfunction "EN_1") (pintype "input"))
    )
    (net (code "29") (name "Net-(U10-SS)") (class "Default")
      (node (ref "C37") (pin "2") (pinfunction "2_2") (pintype "passive"))
      (node (ref "U10") (pin "4") (pinfunction "SS_4") (pintype "input"))
    )
    (net (code "30") (name "Net-(U10-SW)") (class "Default")
      (node (ref "C33") (pin "1") (pinfunction "1_1") (pintype "passive"))
      (node (ref "L2") (pin "1") (pinfunction "1_1") (pintype "passive"))
      (node (ref "U10") (pin "6") (pinfunction "SW_6") (pintype "output"))
    )
    (net (code "31") (name "Net-(U10-VBST)") (class "Default")
      (node (ref "C33") (pin "2") (pinfunction "2_2") (pintype "passive"))
      (node (ref "U10") (pin "7") (pinfunction "VBST_7") (pintype "output"))
    )
    (net (code "32") (name "Net-(U10-VFB)") (class "Default")
      (node (ref "R42") (pin "2") (pinfunction "2_2") (pintype "passive"))
      (node (ref "R43") (pin "2") (pinfunction "2_2") (pintype "passive"))
      (node (ref "U10") (pin "2") (pinfunction "VFB_2") (pintype "input"))
    )
    (net (code "33") (name "Net-(U10-VREG5)") (class "Default")
      (node (ref "C36") (pin "2") (pinfunction "2_2") (pintype "passive"))
      (node (ref "U10") (pin "3") (pinfunction "VREG5_3") (pintype "output"))
    )
    (net (code "34") (name "Net-(U11-P0.0)") (class "Default")
      (node (ref "R37") (pin "1") (pinfunction "1_1") (pintype "passive"))
      (node (ref "U11") (pin "2") (pinfunction "P0.0_2") (pintype "passive"))
    )
    (net (code "35") (name "Net-(U11-P0.1)") (class "Default")
      (node (ref "R38") (pin "1") (pinfunction "1_1") (pintype "passive"))
      (node (ref "U11") (pin "1") (pinfunction "P0.1_1") (pintype "passive"))
    )
    (net (code "36") (name "Net-(U11-P0.2)") (class "Default")
      (node (ref "R39") (pin "1") (pinfunction "1_1") (pintype "passive"))
      (node (ref "U11") (pin "20") (pinfunction "P0.2_20") (pintype "passive"))
    )
    (net (code "37") (name "Net-(U11-P0.3)") (class "Default")
      (node (ref "R44") (pin "2") (pinfunction "2_2") (pintype "passive"))
      (node (ref "U11") (pin "19") (pinfunction "P0.3_19") (pintype "passive"))
    )
    (net (code "38") (name "Net-(U11-P0.6)") (class "Default")
      (node (ref "C29") (pin "1") (pinfunction "1_1") (pintype "passive"))
      (node (ref "R32") (pin "1") (pinfunction "1_1") (pintype "passive"))
      (node (ref "R33") (pin "2") (pinfunction "2_2") (pintype "passive"))
      (node (ref "U11") (pin "16") (pinfunction "P0.6_16") (pintype "passive"))
    )
    (net (code "39") (name "Net-(U11-P1.2)") (class "Default")
      (node (ref "R35") (pin "1") (pinfunction "1_1") (pintype "passive"))
      (node (ref "R47") (pin "2") (pinfunction "2_2") (pintype "passive"))
      (node (ref "U11") (pin "11") (pinfunction "P1.2_11") (pintype "passive"))
    )
    (net (code "40") (name "Net-(U11-P1.5)") (class "Default")
      (node (ref "R46") (pin "2") (pinfunction "2_2") (pintype "passive"))
      (node (ref "U11") (pin "9") (pinfunction "P1.5_9") (pintype "passive"))
      (node (ref "U8") (pin "2") (pinfunction "A_2") (pintype "passive"))
    )
    (net (code "41") (name "Net-(U11-RSTB_{slash}_C2CK)") (class "Default")
      (node (ref "R36") (pin "1") (pinfunction "1_1") (pintype "passive"))
      (node (ref "U11") (pin "5") (pinfunction "RSTB_/_C2CK_5") (pintype "passive"))
    )
    (net (code "42") (name "Net-(U12-NR)") (class "Default")
      (node (ref "C39") (pin "2") (pinfunction "2_2") (pintype "passive"))
      (node (ref "U12") (pin "2") (pinfunction "NR_2") (pintype "passive"))
    )
    (net (code "43") (name "VDD_1V8") (class "Default")
      (node (ref "C42") (pin "2") (pinfunction "2_2") (pintype "passive"))
      (node (ref "U13") (pin "5") (pinfunction "OUT_5") (pintype "power_in"))
    )
    (net (code "44") (name "VDD_3V3_SYS") (class "Default")
      (node (ref "C34") (pin "2") (pinfunction "2_2") (pintype "passive"))
      (node (ref "C35") (pin "2") (pinfunction "2_2") (pintype "passive"))
      (node (ref "C41") (pin "2") (pinfunction "2_2") (pintype "passive"))
      (node (ref "L2") (pin "2") (pinfunction "2_2") (pintype "passive"))
      (node (ref "R34") (pin "2") (pinfunction "2_2") (pintype "passive"))
      (node (ref "R42") (pin "1") (pinfunction "1_1") (pintype "passive"))
      (node (ref "R50") (pin "2") (pinfunction "2_2") (pintype "passive"))
      (node (ref "U13") (pin "1") (pinfunction "IN_1") (pintype "power_in"))
    )
    (net (code "45") (name "VDD_5V_SYS") (class "Default")
      (node (ref "C25") (pin "2") (pinfunction "2_2") (pintype "passive"))
      (node (ref "C26") (pin "2") (pinfunction "2_2") (pintype "passive"))
      (node (ref "C38") (pin "2") (pinfunction "2_2") (pintype "passive"))
      (node (ref "L1") (pin "2") (pinfunction "2_2") (pintype "passive"))
      (node (ref "R24") (pin "2") (pinfunction "2_2") (pintype "passive"))
      (node (ref "R28") (pin "1") (pinfunction "1_1") (pintype "passive"))
      (node (ref "R48") (pin "2") (pinfunction "2_2") (pintype "passive"))
      (node (ref "R49") (pin "2") (pinfunction "2_2") (pintype "passive"))
      (node (ref "U12") (pin "6") (pinfunction "IN_6") (pintype "power_in"))
      (node (ref "U8") (pin "5") (pinfunction "VCC_5") (pintype "passive"))
    )
    (net (code "46") (name "VDD_DCIN") (class "Default")
      (node (ref "C16") (pin "1") (pinfunction "1_1") (pintype "passive"))
      (node (ref "C17") (pin "1") (pinfunction "1_1") (pintype "passive"))
      (node (ref "C21") (pin "2") (pinfunction "2_2") (pintype "passive"))
      (node (ref "C22") (pin "2") (pinfunction "2_2") (pintype "passive"))
      (node (ref "C30") (pin "2") (pinfunction "2_2") (pintype "passive"))
      (node (ref "C31") (pin "2") (pinfunction "2_2") (pintype "passive"))
      (node (ref "Q4") (pin "1-2-5-6") (pinfunction "D_1-2-5-6") (pintype "passive"))
      (node (ref "Q5") (pin "3") (pinfunction "S_3") (pintype "passive"))
      (node (ref "R23") (pin "2") (pinfunction "2_2") (pintype "passive"))
      (node (ref "R27") (pin "2") (pinfunction "2_2") (pintype "passive"))
      (node (ref "R51") (pin "1") (pinfunction "1_1") (pintype "passive"))
      (node (ref "U10") (pin "8") (pinfunction "VIN_8") (pintype "power_in"))
      (node (ref "U5") (pin "8") (pinfunction "VIN_8") (pintype "power_in"))
    )
    (net (code "47") (name "unconnected-(D4-NC-Pad2)") (class "Default")
      (node (ref "D4") (pin "2") (pinfunction "NC_2") (pintype "passive+no_connect"))
    )
    (net (code "48") (name "unconnected-(Q4-S-Pad7)") (class "Default")
      (node (ref "Q4") (pin "7") (pinfunction "S_7") (pintype "passive+no_connect"))
    )
    (net (code "49") (name "unconnected-(U9B-NC-Pad1)") (class "Default")
      (node (ref "U9") (pin "1") (pinfunction "NC_1") (pintype "passive+no_connect"))
    )
    (net (code "50") (name "unconnected-(U11-P1.3-Pad10)") (class "Default")
      (node (ref "U11") (pin "10") (pinfunction "P1.3_10") (pintype "passive+no_connect"))
    )
    (net (code "51") (name "unconnected-(U11-P1.6-Pad8)") (class "Default")
      (node (ref "U11") (pin "8") (pinfunction "P1.6_8") (pintype "passive+no_connect"))
    )
    (net (code "52") (name "unconnected-(U11-P1.7-Pad7)") (class "Default")
      (node (ref "U11") (pin "7") (pinfunction "P1.7_7") (pintype "passive+no_connect"))
    )
    (net (code "53") (name "unconnected-(U11-P2.7_{slash}_C2D-Pad6)") (class "Default")
      (node (ref "U11") (pin "6") (pinfunction "P2.7_/_C2D_6") (pintype "passive+no_connect"))
    )
  )
)
